# CheetahBoosterMCU.net
KiCad netlist of a schematic drawn in EAGLE
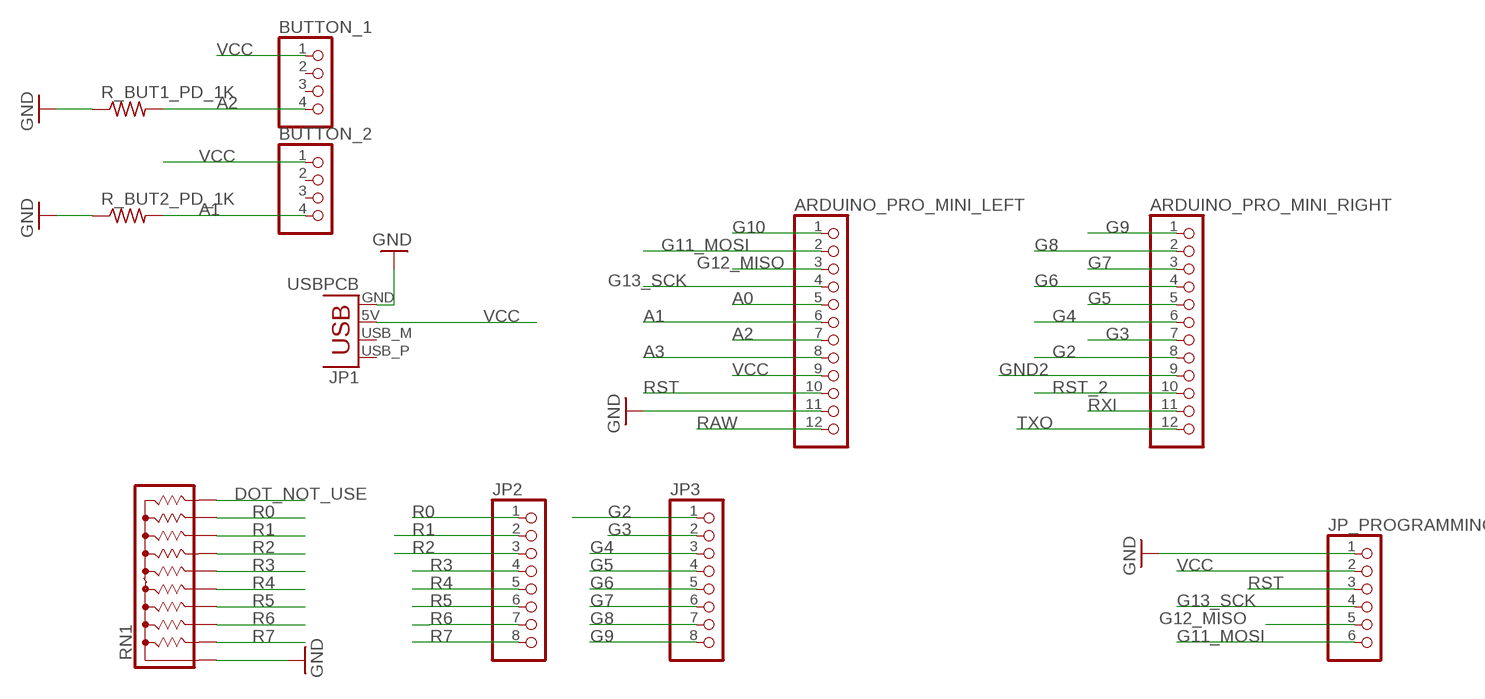
[diagram p0: schematic, sheet 1]

(export (version "E")
  (design (tool "Eeschema 10.0.6"))
  (components
    (comp (ref "ARDUINO_PRO_MINI_LEFT")
      (value "PINHD-1X12")
      (footprint "eagle-import:1X12")
      (libsource (lib "eagle-import") (part "PINHD-1X12"))
    )
    (comp (ref "ARDUINO_PRO_MINI_RIGHT")
      (value "PINHD-1X12")
      (footprint "eagle-import:1X12")
      (libsource (lib "eagle-import") (part "PINHD-1X12"))
    )
    (comp (ref "BUTTON_1")
      (value "PINHD-1X4")
      (footprint "eagle-import:1X04")
      (libsource (lib "eagle-import") (part "PINHD-1X4"))
    )
    (comp (ref "BUTTON_2")
      (value "PINHD-1X4")
      (footprint "eagle-import:1X04")
      (libsource (lib "eagle-import") (part "PINHD-1X4"))
    )
    (comp (ref "JP1")
      (value "USBPCB")
      (footprint "eagle-import:USB-A-PCB")
      (libsource (lib "eagle-import") (part "USBPCB"))
    )
    (comp (ref "JP2")
      (value "PINHD-1X8")
      (footprint "eagle-import:1X08")
      (libsource (lib "eagle-import") (part "PINHD-1X8"))
    )
    (comp (ref "JP3")
      (value "PINHD-1X8")
      (footprint "eagle-import:1X08")
      (libsource (lib "eagle-import") (part "PINHD-1X8"))
    )
    (comp (ref "JP_PROGRAMMING")
      (value "PINHD-1X6")
      (footprint "eagle-import:1X06")
      (libsource (lib "eagle-import") (part "PINHD-1X6"))
    )
    (comp (ref "RN1")
      (value "4610X")
      (footprint "eagle-import:SIP10")
      (libsource (lib "eagle-import") (part "4610X"))
    )
    (comp (ref "R_BUT1_PD_1K")
      (value "R-US_R1206")
      (footprint "eagle-import:R1206")
      (libsource (lib "eagle-import") (part "R-US_R1206"))
    )
    (comp (ref "R_BUT2_PD_1K")
      (value "R-US_R1206")
      (footprint "eagle-import:R1206")
      (libsource (lib "eagle-import") (part "R-US_R1206"))
    )
  )
  (nets
    (net (code "1") (name "/A0") (class "Default")
      (node (ref "ARDUINO_PRO_MINI_LEFT") (pin "5") (pinfunction "5_5") (pintype "passive"))
    )
    (net (code "2") (name "/A1") (class "Default")
      (node (ref "ARDUINO_PRO_MINI_LEFT") (pin "6") (pinfunction "6_6") (pintype "passive"))
      (node (ref "BUTTON_2") (pin "4") (pinfunction "4_4") (pintype "passive"))
      (node (ref "R_BUT2_PD_1K") (pin "2") (pinfunction "2_2") (pintype "passive"))
    )
    (net (code "3") (name "/A2") (class "Default")
      (node (ref "ARDUINO_PRO_MINI_LEFT") (pin "7") (pinfunction "7_7") (pintype "passive"))
      (node (ref "BUTTON_1") (pin "4") (pinfunction "4_4") (pintype "passive"))
      (node (ref "R_BUT1_PD_1K") (pin "2") (pinfunction "2_2") (pintype "passive"))
    )
    (net (code "4") (name "/A3") (class "Default")
      (node (ref "ARDUINO_PRO_MINI_LEFT") (pin "8") (pinfunction "8_8") (pintype "passive"))
    )
    (net (code "5") (name "/DOT_NOT_USE") (class "Default")
      (node (ref "RN1") (pin "10") (pinfunction "10_10") (pintype "passive"))
    )
    (net (code "6") (name "/G2") (class "Default")
      (node (ref "ARDUINO_PRO_MINI_RIGHT") (pin "8") (pinfunction "8_8") (pintype "passive"))
      (node (ref "JP3") (pin "1") (pinfunction "1_1") (pintype "passive"))
    )
    (net (code "7") (name "/G3") (class "Default")
      (node (ref "ARDUINO_PRO_MINI_RIGHT") (pin "7") (pinfunction "7_7") (pintype "passive"))
      (node (ref "JP3") (pin "2") (pinfunction "2_2") (pintype "passive"))
    )
    (net (code "8") (name "/G4") (class "Default")
      (node (ref "ARDUINO_PRO_MINI_RIGHT") (pin "6") (pinfunction "6_6") (pintype "passive"))
      (node (ref "JP3") (pin "3") (pinfunction "3_3") (pintype "passive"))
    )
    (net (code "9") (name "/G5") (class "Default")
      (node (ref "ARDUINO_PRO_MINI_RIGHT") (pin "5") (pinfunction "5_5") (pintype "passive"))
      (node (ref "JP3") (pin "4") (pinfunction "4_4") (pintype "passive"))
    )
    (net (code "10") (name "/G6") (class "Default")
      (node (ref "ARDUINO_PRO_MINI_RIGHT") (pin "4") (pinfunction "4_4") (pintype "passive"))
      (node (ref "JP3") (pin "5") (pinfunction "5_5") (pintype "passive"))
    )
    (net (code "11") (name "/G7") (class "Default")
      (node (ref "ARDUINO_PRO_MINI_RIGHT") (pin "3") (pinfunction "3_3") (pintype "passive"))
      (node (ref "JP3") (pin "6") (pinfunction "6_6") (pintype "passive"))
    )
    (net (code "12") (name "/G8") (class "Default")
      (node (ref "ARDUINO_PRO_MINI_RIGHT") (pin "2") (pinfunction "2_2") (pintype "passive"))
      (node (ref "JP3") (pin "7") (pinfunction "7_7") (pintype "passive"))
    )
    (net (code "13") (name "/G9") (class "Default")
      (node (ref "ARDUINO_PRO_MINI_RIGHT") (pin "1") (pinfunction "1_1") (pintype "passive"))
      (node (ref "JP3") (pin "8") (pinfunction "8_8") (pintype "passive"))
    )
    (net (code "14") (name "/G10") (class "Default")
      (node (ref "ARDUINO_PRO_MINI_LEFT") (pin "1") (pinfunction "1_1") (pintype "passive"))
    )
    (net (code "15") (name "/G11_MOSI") (class "Default")
      (node (ref "ARDUINO_PRO_MINI_LEFT") (pin "2") (pinfunction "2_2") (pintype "passive"))
      (node (ref "JP_PROGRAMMING") (pin "6") (pinfunction "6_6") (pintype "passive"))
    )
    (net (code "16") (name "/G12_MISO") (class "Default")
      (node (ref "ARDUINO_PRO_MINI_LEFT") (pin "3") (pinfunction "3_3") (pintype "passive"))
      (node (ref "JP_PROGRAMMING") (pin "5") (pinfunction "5_5") (pintype "passive"))
    )
    (net (code "17") (name "/G13_SCK") (class "Default")
      (node (ref "ARDUINO_PRO_MINI_LEFT") (pin "4") (pinfunction "4_4") (pintype "passive"))
      (node (ref "JP_PROGRAMMING") (pin "4") (pinfunction "4_4") (pintype "passive"))
    )
    (net (code "18") (name "/GND2") (class "Default")
      (node (ref "ARDUINO_PRO_MINI_RIGHT") (pin "9") (pinfunction "9_9") (pintype "passive"))
    )
    (net (code "19") (name "/R0") (class "Default")
      (node (ref "JP2") (pin "1") (pinfunction "1_1") (pintype "passive"))
      (node (ref "RN1") (pin "9") (pinfunction "9_9") (pintype "passive"))
    )
    (net (code "20") (name "/R1") (class "Default")
      (node (ref "JP2") (pin "2") (pinfunction "2_2") (pintype "passive"))
      (node (ref "RN1") (pin "8") (pinfunction "8_8") (pintype "passive"))
    )
    (net (code "21") (name "/R2") (class "Default")
      (node (ref "JP2") (pin "3") (pinfunction "3_3") (pintype "passive"))
      (node (ref "RN1") (pin "7") (pinfunction "7_7") (pintype "passive"))
    )
    (net (code "22") (name "/R3") (class "Default")
      (node (ref "JP2") (pin "4") (pinfunction "4_4") (pintype "passive"))
      (node (ref "RN1") (pin "6") (pinfunction "6_6") (pintype "passive"))
    )
    (net (code "23") (name "/R4") (class "Default")
      (node (ref "JP2") (pin "5") (pinfunction "5_5") (pintype "passive"))
      (node (ref "RN1") (pin "5") (pinfunction "5_5") (pintype "passive"))
    )
    (net (code "24") (name "/R5") (class "Default")
      (node (ref "JP2") (pin "6") (pinfunction "6_6") (pintype "passive"))
      (node (ref "RN1") (pin "4") (pinfunction "4_4") (pintype "passive"))
    )
    (net (code "25") (name "/R6") (class "Default")
      (node (ref "JP2") (pin "7") (pinfunction "7_7") (pintype "passive"))
      (node (ref "RN1") (pin "3") (pinfunction "3_3") (pintype "passive"))
    )
    (net (code "26") (name "/R7") (class "Default")
      (node (ref "JP2") (pin "8") (pinfunction "8_8") (pintype "passive"))
      (node (ref "RN1") (pin "2") (pinfunction "2_2") (pintype "passive"))
    )
    (net (code "27") (name "/RAW") (class "Default")
      (node (ref "ARDUINO_PRO_MINI_LEFT") (pin "12") (pinfunction "12_12") (pintype "passive"))
    )
    (net (code "28") (name "/RST") (class "Default")
      (node (ref "ARDUINO_PRO_MINI_LEFT") (pin "10") (pinfunction "10_10") (pintype "passive"))
      (node (ref "JP_PROGRAMMING") (pin "3") (pinfunction "3_3") (pintype "passive"))
    )
    (net (code "29") (name "/RST_2") (class "Default")
      (node (ref "ARDUINO_PRO_MINI_RIGHT") (pin "10") (pinfunction "10_10") (pintype "passive"))
    )
    (net (code "30") (name "/RXI") (class "Default")
      (node (ref "ARDUINO_PRO_MINI_RIGHT") (pin "11") (pinfunction "11_11") (pintype "passive"))
    )
    (net (code "31") (name "/TXO") (class "Default")
      (node (ref "ARDUINO_PRO_MINI_RIGHT") (pin "12") (pinfunction "12_12") (pintype "passive"))
    )
    (net (code "32") (name "/VCC") (class "Default")
      (node (ref "ARDUINO_PRO_MINI_LEFT") (pin "9") (pinfunction "9_9") (pintype "passive"))
      (node (ref "BUTTON_1") (pin "1") (pinfunction "1_1") (pintype "passive"))
      (node (ref "BUTTON_2") (pin "1") (pinfunction "1_1") (pintype "passive"))
      (node (ref "JP1") (pin "5V") (pinfunction "VBUS_5V") (pintype "bidirectional"))
      (node (ref "JP_PROGRAMMING") (pin "2") (pinfunction "2_2") (pintype "passive"))
    )
    (net (code "33") (name "GND") (class "Default")
      (node (ref "ARDUINO_PRO_MINI_LEFT") (pin "11") (pinfunction "11_11") (pintype "passive"))
      (node (ref "JP1") (pin "GND") (pinfunction "GND_GND") (pintype "bidirectional"))
      (node (ref "JP_PROGRAMMING") (pin "1") (pinfunction "1_1") (pintype "passive"))
      (node (ref "RN1") (pin "1") (pinfunction "1_1") (pintype "passive"))
      (node (ref "R_BUT1_PD_1K") (pin "1") (pinfunction "1_1") (pintype "passive"))
      (node (ref "R_BUT2_PD_1K") (pin "1") (pinfunction "1_1") (pintype "passive"))
    )
    (net (code "34") (name "unconnected-(BUTTON_1-Pad2)") (class "Default")
      (node (ref "BUTTON_1") (pin "2") (pinfunction "2_2") (pintype "passive"))
    )
    (net (code "35") (name "unconnected-(BUTTON_1-Pad3)") (class "Default")
      (node (ref "BUTTON_1") (pin "3") (pinfunction "3_3") (pintype "passive"))
    )
    (net (code "36") (name "unconnected-(BUTTON_2-Pad2)") (class "Default")
      (node (ref "BUTTON_2") (pin "2") (pinfunction "2_2") (pintype "passive"))
    )
    (net (code "37") (name "unconnected-(BUTTON_2-Pad3)") (class "Default")
      (node (ref "BUTTON_2") (pin "3") (pinfunction "3_3") (pintype "passive"))
    )
    (net (code "38") (name "unconnected-(JP1-D+-PadUSB_P)") (class "Default")
      (node (ref "JP1") (pin "USB_P") (pinfunction "D+_USB_P") (pintype "bidirectional"))
    )
    (net (code "39") (name "unconnected-(JP1-D--PadUSB_M)") (class "Default")
      (node (ref "JP1") (pin "USB_M") (pinfunction "D-_USB_M") (pintype "bidirectional"))
    )
  )
)
